# triBot-v2-1.net
KiCad netlist of a schematic drawn in EAGLE
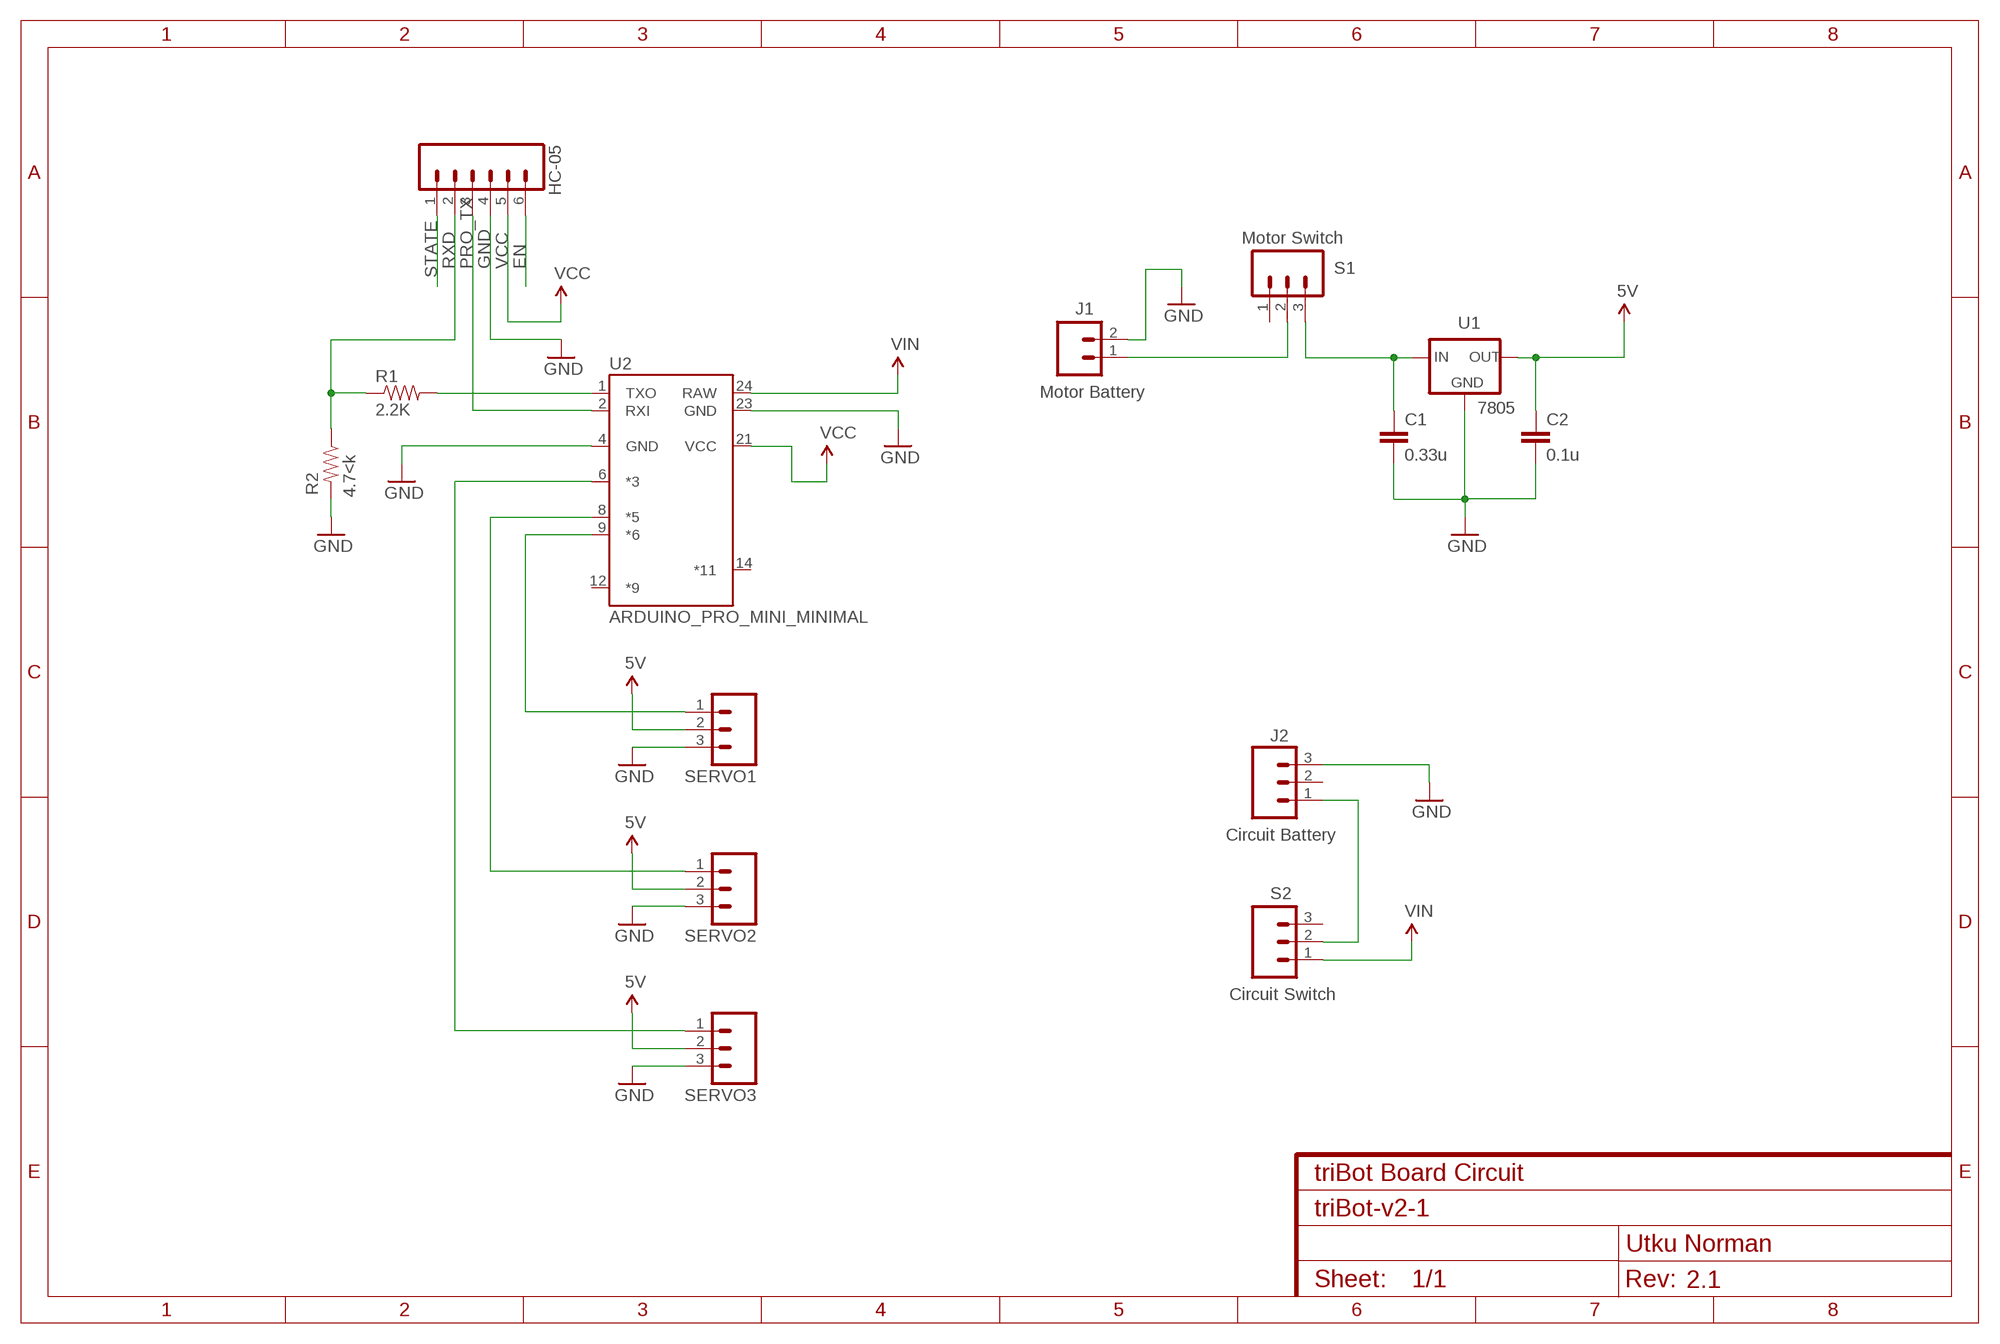
[diagram p0: schematic, sheet 1]

(export (version "E")
  (design (tool "Eeschema 10.0.6"))
  (components
    (comp (ref "C1")
      (value "0.33u")
      (footprint "eagle-import:CAP-PTH-SMALL")
      (libsource (lib "eagle-import") (part "CAPPTH"))
    )
    (comp (ref "C2")
      (value "0.1u")
      (footprint "eagle-import:CAP-PTH-SMALL")
      (libsource (lib "eagle-import") (part "CAPPTH"))
    )
    (comp (ref "HC-05")
      (value "M06LOCK_LONGPADS")
      (footprint "eagle-import:1X06_LOCK_LONGPADS")
      (libsource (lib "eagle-import") (part "M06LOCK_LONGPADS"))
    )
    (comp (ref "J1")
      (value "Motor Battery")
      (footprint "eagle-import:SCREWTERMINAL-5MM-2")
      (libsource (lib "eagle-import") (part "M025MM"))
    )
    (comp (ref "J2")
      (value "Circuit Battery")
      (footprint "eagle-import:1X03_LONGPADS")
      (libsource (lib "eagle-import") (part "M03LONGPADS"))
    )
    (comp (ref "R1")
      (value "2.2K")
      (footprint "eagle-import:AXIAL-0.3-KIT")
      (libsource (lib "eagle-import") (part "RESISTORKIT"))
    )
    (comp (ref "R2")
      (value "4.7<k")
      (footprint "eagle-import:AXIAL-0.3-KIT")
      (libsource (lib "eagle-import") (part "RESISTORKIT"))
    )
    (comp (ref "S1")
      (value "Motor Switch")
      (footprint "eagle-import:SCREWTERMINAL-5MM-3")
      (libsource (lib "eagle-import") (part "M03-SCREW-5MM"))
    )
    (comp (ref "S2")
      (value "Circuit Switch")
      (footprint "eagle-import:1X03_LOCK_LONGPADS")
      (libsource (lib "eagle-import") (part "M03LOCK_LONGPADS"))
    )
    (comp (ref "SERVO1")
      (value "M03LONGPADS")
      (footprint "eagle-import:1X03_LONGPADS")
      (libsource (lib "eagle-import") (part "M03LONGPADS"))
    )
    (comp (ref "SERVO2")
      (value "M03LONGPADS")
      (footprint "eagle-import:1X03_LONGPADS")
      (libsource (lib "eagle-import") (part "M03LONGPADS"))
    )
    (comp (ref "SERVO3")
      (value "M03LONGPADS")
      (footprint "eagle-import:1X03_LONGPADS")
      (libsource (lib "eagle-import") (part "M03LONGPADS"))
    )
    (comp (ref "U1")
      (value "7805")
      (footprint "eagle-import:TO-220-ALT")
      (libsource (lib "eagle-import") (part "V_REG_78XX-TO-220"))
    )
    (comp (ref "U2")
      (value "ARDUINO_PRO_MINI_MINIMAL")
      (footprint "eagle-import:ARDUINO_PRO_MINI_MINIMAL")
      (libsource (lib "eagle-import") (part "ARDUINO_PRO_MINI_MINIMAL"))
    )
  )
  (nets
    (net (code "1") (name "/EN") (class "Default")
      (node (ref "HC-05") (pin "6") (pinfunction "6_6") (pintype "passive"))
    )
    (net (code "2") (name "/PRO_TX") (class "Default")
      (node (ref "R1") (pin "P$2") (pinfunction "2_P$2") (pintype "passive"))
      (node (ref "U2") (pin "1") (pinfunction "TXO_1") (pintype "bidirectional"))
    )
    (net (code "3") (name "/RXD") (class "Default")
      (node (ref "HC-05") (pin "2") (pinfunction "2_2") (pintype "passive"))
      (node (ref "R1") (pin "P$1") (pinfunction "1_P$1") (pintype "passive"))
      (node (ref "R2") (pin "P$1") (pinfunction "1_P$1") (pintype "passive"))
    )
    (net (code "4") (name "/STATE") (class "Default")
      (node (ref "HC-05") (pin "1") (pinfunction "1_1") (pintype "passive"))
    )
    (net (code "5") (name "5V") (class "Default")
      (node (ref "C2") (pin "1") (pinfunction "1_1") (pintype "passive"))
      (node (ref "SERVO1") (pin "2") (pinfunction "2_2") (pintype "passive"))
      (node (ref "SERVO2") (pin "2") (pinfunction "2_2") (pintype "passive"))
      (node (ref "SERVO3") (pin "2") (pinfunction "2_2") (pintype "passive"))
      (node (ref "U1") (pin "OUT") (pinfunction "OUT_OUT") (pintype "passive"))
    )
    (net (code "6") (name "GND") (class "Default")
      (node (ref "C1") (pin "2") (pinfunction "2_2") (pintype "passive"))
      (node (ref "C2") (pin "2") (pinfunction "2_2") (pintype "passive"))
      (node (ref "HC-05") (pin "4") (pinfunction "4_4") (pintype "passive"))
      (node (ref "J1") (pin "2") (pinfunction "2_2") (pintype "passive"))
      (node (ref "J2") (pin "3") (pinfunction "3_3") (pintype "passive"))
      (node (ref "R2") (pin "P$2") (pinfunction "2_P$2") (pintype "passive"))
      (node (ref "SERVO1") (pin "3") (pinfunction "3_3") (pintype "passive"))
      (node (ref "SERVO2") (pin "3") (pinfunction "3_3") (pintype "passive"))
      (node (ref "SERVO3") (pin "3") (pinfunction "3_3") (pintype "passive"))
      (node (ref "U1") (pin "GND") (pinfunction "GND_GND") (pintype "input"))
      (node (ref "U2") (pin "23") (pinfunction "GND_23") (pintype "bidirectional"))
      (node (ref "U2") (pin "4") (pinfunction "GND_4") (pintype "bidirectional"))
    )
    (net (code "7") (name "Net-(C1-Pad1)") (class "Default")
      (node (ref "C1") (pin "1") (pinfunction "1_1") (pintype "passive"))
      (node (ref "S1") (pin "3") (pinfunction "3_3") (pintype "passive"))
      (node (ref "U1") (pin "IN") (pinfunction "IN_IN") (pintype "input"))
    )
    (net (code "8") (name "Net-(J1-Pad1)") (class "Default")
      (node (ref "J1") (pin "1") (pinfunction "1_1") (pintype "passive"))
      (node (ref "S1") (pin "2") (pinfunction "2_2") (pintype "passive"))
    )
    (net (code "9") (name "Net-(J2-Pad1)") (class "Default")
      (node (ref "J2") (pin "1") (pinfunction "1_1") (pintype "passive"))
      (node (ref "S2") (pin "2") (pinfunction "2_2") (pintype "passive"))
    )
    (net (code "10") (name "Net-(U2-*3)") (class "Default")
      (node (ref "SERVO3") (pin "1") (pinfunction "1_1") (pintype "passive"))
      (node (ref "U2") (pin "6") (pinfunction "*3_6") (pintype "bidirectional"))
    )
    (net (code "11") (name "Net-(U2-*5)") (class "Default")
      (node (ref "SERVO2") (pin "1") (pinfunction "1_1") (pintype "passive"))
      (node (ref "U2") (pin "8") (pinfunction "*5_8") (pintype "bidirectional"))
    )
    (net (code "12") (name "Net-(U2-*6)") (class "Default")
      (node (ref "SERVO1") (pin "1") (pinfunction "1_1") (pintype "passive"))
      (node (ref "U2") (pin "9") (pinfunction "*6_9") (pintype "bidirectional"))
    )
    (net (code "13") (name "Net-(U2-RXI)") (class "Default")
      (node (ref "HC-05") (pin "3") (pinfunction "3_3") (pintype "passive"))
      (node (ref "U2") (pin "2") (pinfunction "RXI_2") (pintype "bidirectional"))
    )
    (net (code "14") (name "VCC") (class "Default")
      (node (ref "HC-05") (pin "5") (pinfunction "5_5") (pintype "passive"))
      (node (ref "U2") (pin "21") (pinfunction "VCC_21") (pintype "bidirectional"))
    )
    (net (code "15") (name "VIN") (class "Default")
      (node (ref "S2") (pin "1") (pinfunction "1_1") (pintype "passive"))
      (node (ref "U2") (pin "24") (pinfunction "RAW_24") (pintype "bidirectional"))
    )
    (net (code "16") (name "unconnected-(J2-Pad2)") (class "Default")
      (node (ref "J2") (pin "2") (pinfunction "2_2") (pintype "passive"))
    )
    (net (code "17") (name "unconnected-(S1-Pad1)") (class "Default")
      (node (ref "S1") (pin "1") (pinfunction "1_1") (pintype "passive"))
    )
    (net (code "18") (name "unconnected-(S2-Pad3)") (class "Default")
      (node (ref "S2") (pin "3") (pinfunction "3_3") (pintype "passive"))
    )
    (net (code "19") (name "unconnected-(U2-*9-Pad12)") (class "Default")
      (node (ref "U2") (pin "12") (pinfunction "*9_12") (pintype "bidirectional"))
    )
    (net (code "20") (name "unconnected-(U2-*11-Pad14)") (class "Default")
      (node (ref "U2") (pin "14") (pinfunction "*11_14") (pintype "bidirectional"))
    )
  )
)
